# SCH_cherry1_2026-04-12.net
KiCad netlist of a schematic drawn in EasyEDA
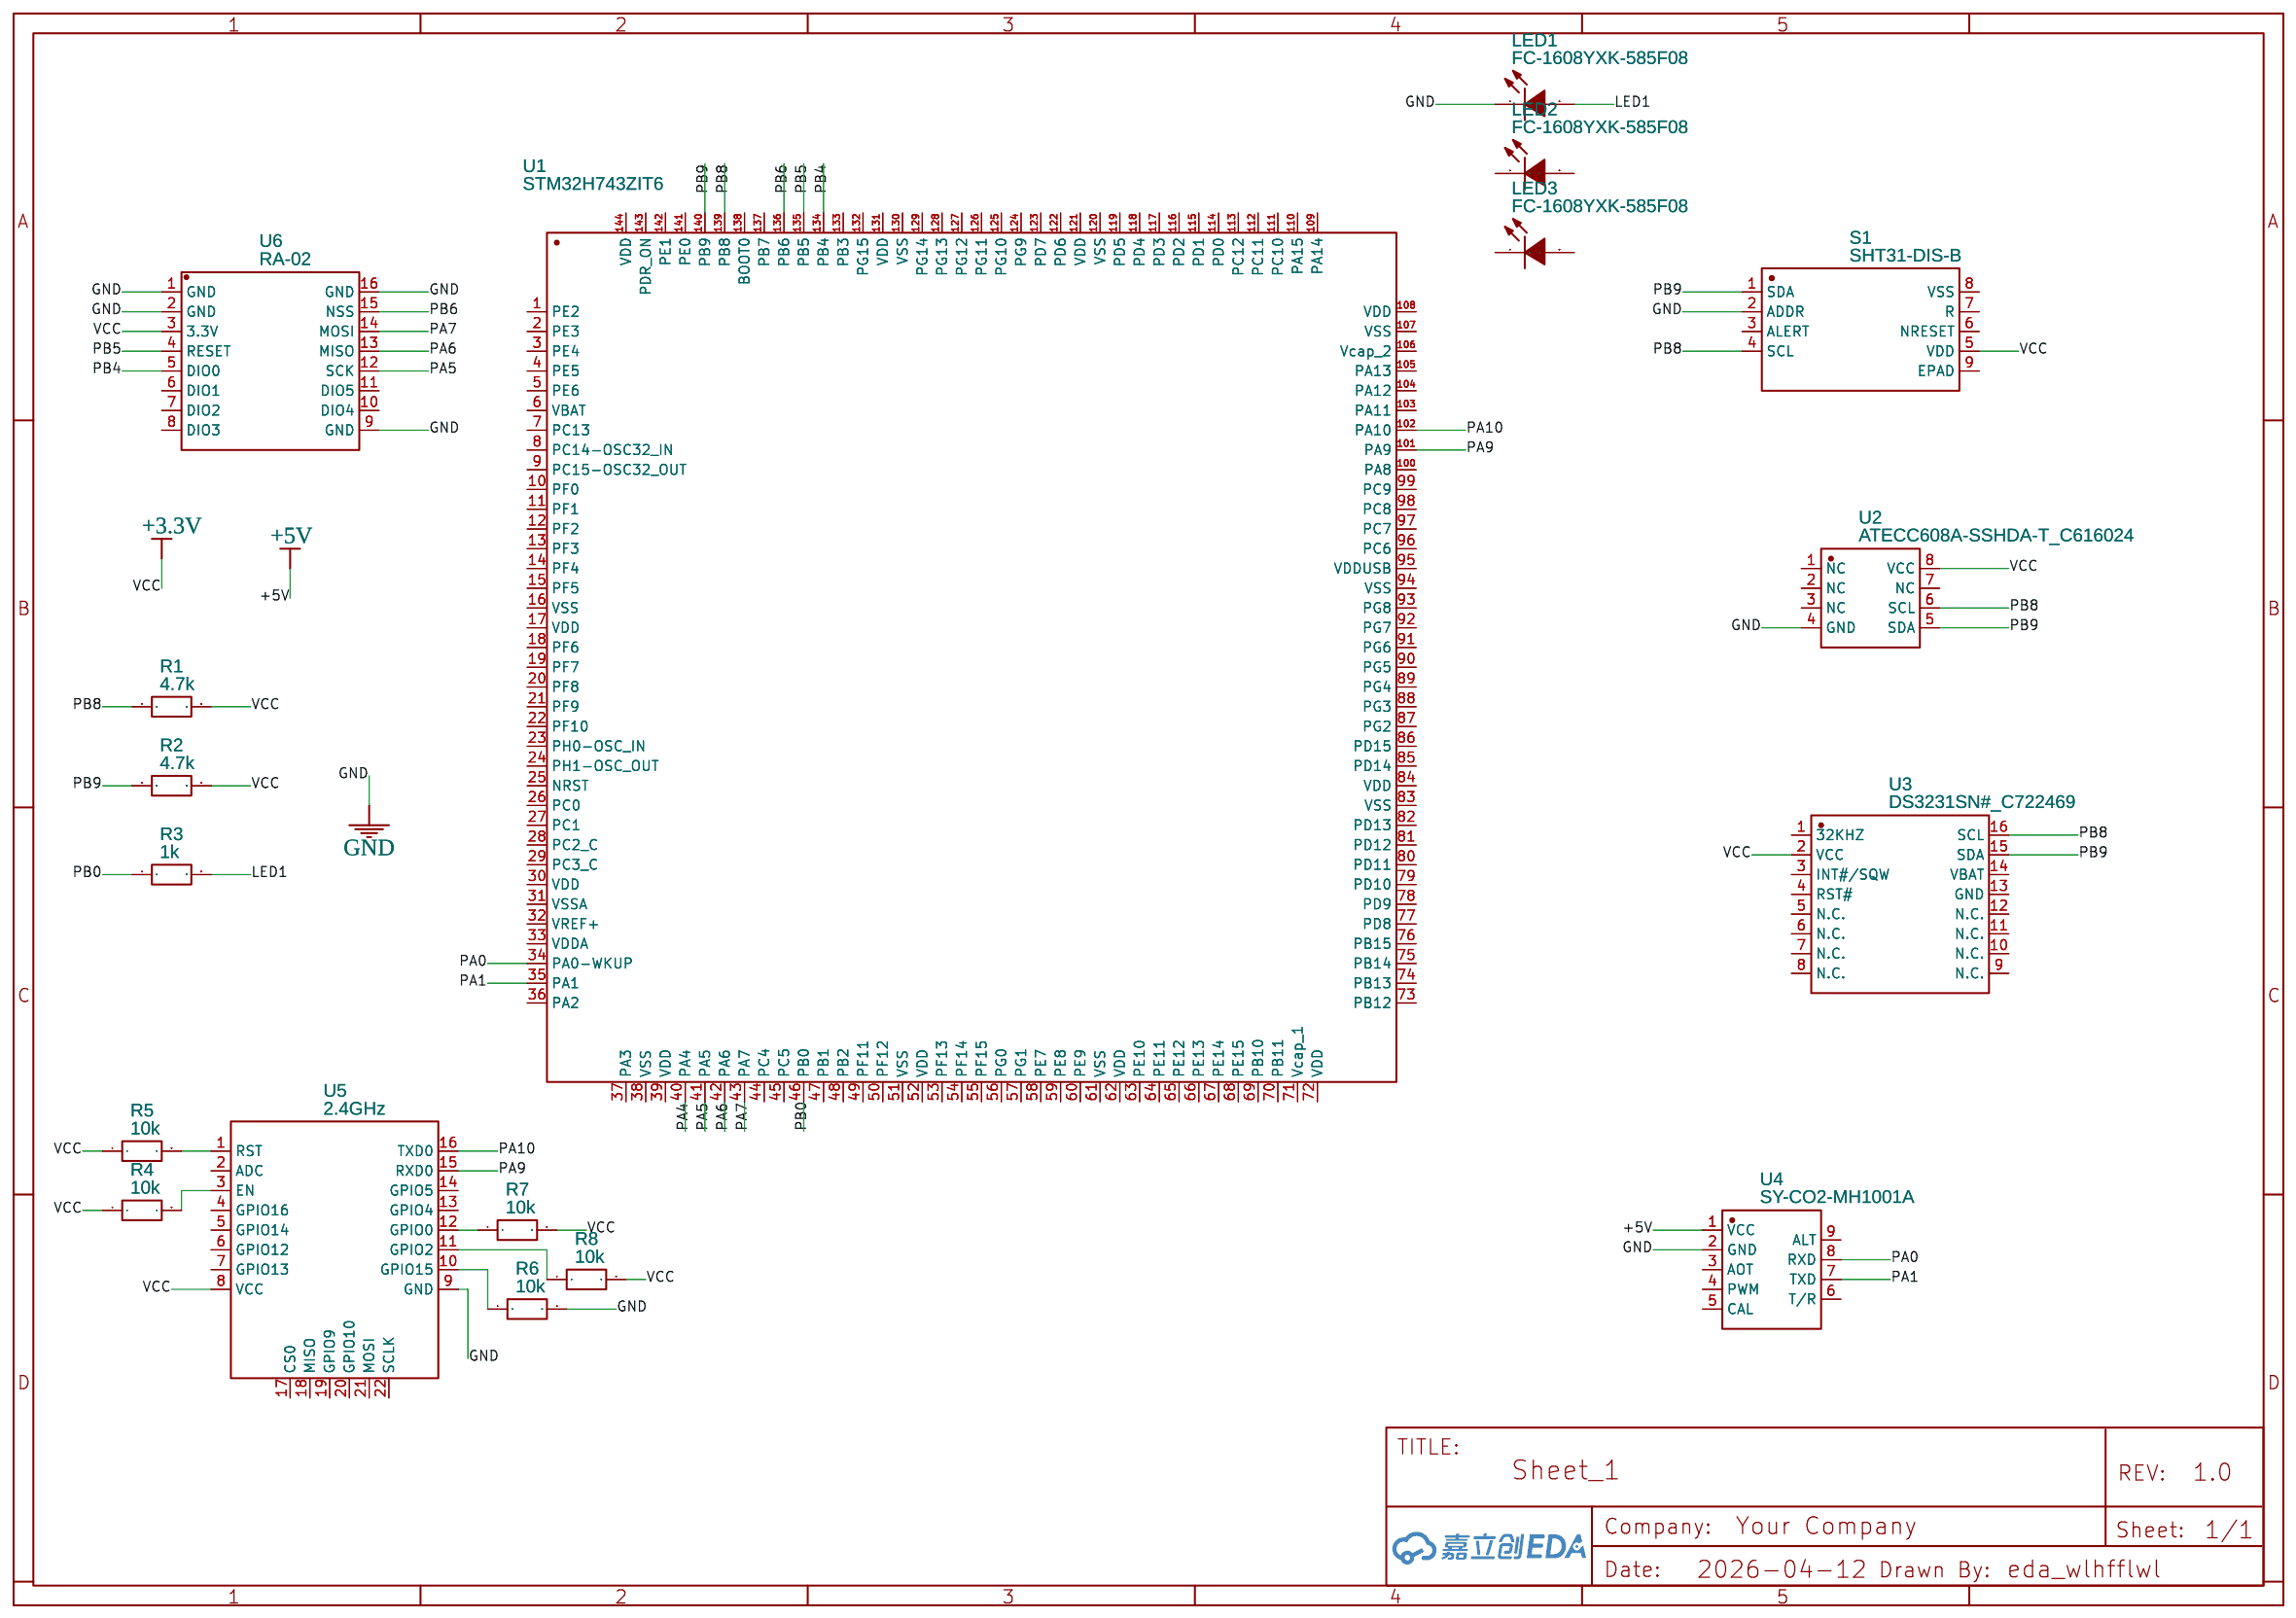
[diagram p0: schematic sheet]

(export (version "E")
  (design (tool "Eeschema 10.0.6"))
  (components
    (comp (ref "LED1")
      (value "FC-1608YXK-585F08")
      (fields (field (name "Manufacturer Part") "NCD0603Y2") (field (name "Manufacturer") "国星光电"))
      (libsource (lib "") (part "FC-1608YXK-585F08"))
    )
    (comp (ref "LED2")
      (value "FC-1608YXK-585F08")
      (fields (field (name "Manufacturer Part") "NCD0603Y2") (field (name "Manufacturer") "国星光电"))
      (libsource (lib "") (part "FC-1608YXK-585F08"))
    )
    (comp (ref "LED3")
      (value "FC-1608YXK-585F08")
      (fields (field (name "Manufacturer Part") "NCD0603Y2") (field (name "Manufacturer") "国星光电"))
      (libsource (lib "") (part "FC-1608YXK-585F08"))
    )
    (comp (ref "R1") (value "4.7k") (libsource (lib "") (part "R_0603_EU")))
    (comp (ref "R2") (value "4.7k") (libsource (lib "") (part "R_0603_EU")))
    (comp (ref "R3") (value "1k") (libsource (lib "") (part "R_0603_EU")))
    (comp (ref "R4") (value "10k") (libsource (lib "") (part "R_0603_EU")))
    (comp (ref "R5") (value "10k") (libsource (lib "") (part "R_0603_EU")))
    (comp (ref "R6") (value "10k") (libsource (lib "") (part "R_0603_EU")))
    (comp (ref "R7") (value "10k") (libsource (lib "") (part "R_0603_EU")))
    (comp (ref "R8") (value "10k") (libsource (lib "") (part "R_0603_EU")))
    (comp (ref "S1")
      (value "SHT31-DIS-B")
      (fields
        (field (name "Manufacturer Part") "SHT31-DIS-B2.5kS")
        (field (name "Manufacturer") "Sensirion(瑞士盛思锐)")
      )
      (libsource (lib "") (part "SHT31-DIS-B"))
    )
    (comp (ref "U1")
      (value "STM32H743ZIT6")
      (fields (field (name "Manufacturer") "ST(意法半导体)"))
      (libsource (lib "") (part "STM32H743ZIT6"))
    )
    (comp (ref "U2")
      (value "ATECC608A-SSHDA-T_C616024")
      (fields
        (field (name "Manufacturer Part") "ATECC608A-SSHDA-T")
        (field (name "Manufacturer") "MICROCHIP(美国微芯)")
      )
      (libsource (lib "") (part "ATECC608A-SSHDA-T_C616024"))
    )
    (comp (ref "U3")
      (value "DS3231SN#_C722469")
      (fields
        (field (name "Manufacturer Part") "DS3231SN#")
        (field (name "Manufacturer") "ADI(亚德诺)/MAXIM(美信)")
      )
      (libsource (lib "") (part "DS3231SN#_C722469"))
    )
    (comp (ref "U4")
      (value "SY-CO2-MH1001A")
      (fields (field (name "Manufacturer Part") "SY-CO2-28BMI") (field (name "Manufacturer") "saiya(赛亚)"))
      (libsource (lib "") (part "SY-CO2-MH1001A"))
    )
    (comp (ref "U5")
      (value "2.4GHz")
      (fields
        (field (name "Manufacturer Part") "ESP-12F(ESP8266MOD)")
        (field (name "Manufacturer") "Ai-Thinker(安信可)")
      )
      (libsource (lib "") (part "ESP-12F(ESP8266MOD)"))
    )
    (comp (ref "U6")
      (value "RA-02")
      (fields (field (name "Manufacturer Part") "Ra-02") (field (name "Manufacturer") "Ai-Thinker(安信可)"))
      (libsource (lib "") (part "RA-02"))
    )
  )
  (nets
    (net (code "1") (name "+3.3V") (class "Default")
      (node (ref "R1") (pin "2") (pinfunction "2_2") (pintype "unspecified"))
      (node (ref "R2") (pin "2") (pinfunction "2_2") (pintype "unspecified"))
      (node (ref "R4") (pin "1") (pinfunction "1_1") (pintype "unspecified"))
      (node (ref "R5") (pin "1") (pinfunction "1_1") (pintype "unspecified"))
      (node (ref "R7") (pin "2") (pinfunction "2_2") (pintype "unspecified"))
      (node (ref "R8") (pin "2") (pinfunction "2_2") (pintype "unspecified"))
      (node (ref "S1") (pin "5") (pinfunction "VDD_5") (pintype "unspecified"))
      (node (ref "U2") (pin "8") (pinfunction "VCC_8") (pintype "unspecified"))
      (node (ref "U3") (pin "2") (pinfunction "VCC_2") (pintype "unspecified"))
      (node (ref "U5") (pin "8") (pinfunction "VCC_8") (pintype "unspecified"))
      (node (ref "U6") (pin "3") (pinfunction "3.3V_3") (pintype "unspecified"))
    )
    (net (code "2") (name "+5V") (class "Default")
      (node (ref "U4") (pin "1") (pinfunction "VCC_1") (pintype "unspecified"))
    )
    (net (code "3") (name "/LED1") (class "Default")
      (node (ref "LED1") (pin "2") (pinfunction "A_2") (pintype "unspecified"))
      (node (ref "R3") (pin "2") (pinfunction "2_2") (pintype "unspecified"))
    )
    (net (code "4") (name "/PA0") (class "Default")
      (node (ref "U1") (pin "34") (pinfunction "PA0-WKUP_34") (pintype "unspecified"))
      (node (ref "U4") (pin "8") (pinfunction "RXD_8") (pintype "unspecified"))
    )
    (net (code "5") (name "/PA1") (class "Default")
      (node (ref "U1") (pin "35") (pinfunction "PA1_35") (pintype "unspecified"))
      (node (ref "U4") (pin "7") (pinfunction "TXD_7") (pintype "unspecified"))
    )
    (net (code "6") (name "/PA4") (class "Default")
      (node (ref "U1") (pin "40") (pinfunction "PA4_40") (pintype "unspecified"))
    )
    (net (code "7") (name "/PA5") (class "Default")
      (node (ref "U1") (pin "41") (pinfunction "PA5_41") (pintype "unspecified"))
      (node (ref "U6") (pin "12") (pinfunction "SCK_12") (pintype "unspecified"))
    )
    (net (code "8") (name "/PA6") (class "Default")
      (node (ref "U1") (pin "42") (pinfunction "PA6_42") (pintype "unspecified"))
      (node (ref "U6") (pin "13") (pinfunction "MISO_13") (pintype "unspecified"))
    )
    (net (code "9") (name "/PA7") (class "Default")
      (node (ref "U1") (pin "43") (pinfunction "PA7_43") (pintype "unspecified"))
      (node (ref "U6") (pin "14") (pinfunction "MOSI_14") (pintype "unspecified"))
    )
    (net (code "10") (name "/PA9") (class "Default")
      (node (ref "U1") (pin "101") (pinfunction "PA9_101") (pintype "unspecified"))
      (node (ref "U5") (pin "15") (pinfunction "RXD0_15") (pintype "unspecified"))
    )
    (net (code "11") (name "/PA10") (class "Default")
      (node (ref "U1") (pin "102") (pinfunction "PA10_102") (pintype "unspecified"))
      (node (ref "U5") (pin "16") (pinfunction "TXD0_16") (pintype "unspecified"))
    )
    (net (code "12") (name "/PB0") (class "Default")
      (node (ref "R3") (pin "1") (pinfunction "1_1") (pintype "unspecified"))
      (node (ref "U1") (pin "46") (pinfunction "PB0_46") (pintype "unspecified"))
    )
    (net (code "13") (name "/PB4") (class "Default")
      (node (ref "U1") (pin "134") (pinfunction "PB4_134") (pintype "unspecified"))
      (node (ref "U6") (pin "5") (pinfunction "DIO0_5") (pintype "unspecified"))
    )
    (net (code "14") (name "/PB5") (class "Default")
      (node (ref "U1") (pin "135") (pinfunction "PB5_135") (pintype "unspecified"))
      (node (ref "U6") (pin "4") (pinfunction "RESET_4") (pintype "unspecified"))
    )
    (net (code "15") (name "/PB6") (class "Default")
      (node (ref "U1") (pin "136") (pinfunction "PB6_136") (pintype "unspecified"))
      (node (ref "U6") (pin "15") (pinfunction "NSS_15") (pintype "unspecified"))
    )
    (net (code "16") (name "/PB8") (class "Default")
      (node (ref "R1") (pin "1") (pinfunction "1_1") (pintype "unspecified"))
      (node (ref "S1") (pin "4") (pinfunction "SCL_4") (pintype "unspecified"))
      (node (ref "U1") (pin "139") (pinfunction "PB8_139") (pintype "unspecified"))
      (node (ref "U2") (pin "6") (pinfunction "SCL_6") (pintype "unspecified"))
      (node (ref "U3") (pin "16") (pinfunction "SCL_16") (pintype "unspecified"))
    )
    (net (code "17") (name "/PB9") (class "Default")
      (node (ref "R2") (pin "1") (pinfunction "1_1") (pintype "unspecified"))
      (node (ref "S1") (pin "1") (pinfunction "SDA_1") (pintype "unspecified"))
      (node (ref "U1") (pin "140") (pinfunction "PB9_140") (pintype "unspecified"))
      (node (ref "U2") (pin "5") (pinfunction "SDA_5") (pintype "unspecified"))
      (node (ref "U3") (pin "15") (pinfunction "SDA_15") (pintype "unspecified"))
    )
    (net (code "18") (name "GND") (class "Default")
      (node (ref "LED1") (pin "1") (pinfunction "K_1") (pintype "unspecified"))
      (node (ref "R6") (pin "2") (pinfunction "2_2") (pintype "unspecified"))
      (node (ref "S1") (pin "2") (pinfunction "ADDR_2") (pintype "unspecified"))
      (node (ref "U2") (pin "4") (pinfunction "GND_4") (pintype "unspecified"))
      (node (ref "U4") (pin "2") (pinfunction "GND_2") (pintype "unspecified"))
      (node (ref "U5") (pin "9") (pinfunction "GND_9") (pintype "unspecified"))
      (node (ref "U6") (pin "1") (pinfunction "GND_1") (pintype "unspecified"))
      (node (ref "U6") (pin "16") (pinfunction "GND_16") (pintype "unspecified"))
      (node (ref "U6") (pin "2") (pinfunction "GND_2") (pintype "unspecified"))
      (node (ref "U6") (pin "9") (pinfunction "GND_9") (pintype "unspecified"))
    )
    (net (code "19") (name "Net-(U5-EN)") (class "Default")
      (node (ref "R4") (pin "2") (pinfunction "2_2") (pintype "unspecified"))
      (node (ref "U5") (pin "3") (pinfunction "EN_3") (pintype "unspecified"))
    )
    (net (code "20") (name "Net-(U5-GPIO0)") (class "Default")
      (node (ref "R7") (pin "1") (pinfunction "1_1") (pintype "unspecified"))
      (node (ref "U5") (pin "12") (pinfunction "GPIO0_12") (pintype "unspecified"))
    )
    (net (code "21") (name "Net-(U5-GPIO2)") (class "Default")
      (node (ref "R8") (pin "1") (pinfunction "1_1") (pintype "unspecified"))
      (node (ref "U5") (pin "11") (pinfunction "GPIO2_11") (pintype "unspecified"))
    )
    (net (code "22") (name "Net-(U5-GPIO15)") (class "Default")
      (node (ref "R6") (pin "1") (pinfunction "1_1") (pintype "unspecified"))
      (node (ref "U5") (pin "10") (pinfunction "GPIO15_10") (pintype "unspecified"))
    )
    (net (code "23") (name "Net-(U5-RST)") (class "Default")
      (node (ref "R5") (pin "2") (pinfunction "2_2") (pintype "unspecified"))
      (node (ref "U5") (pin "1") (pinfunction "RST_1") (pintype "unspecified"))
    )
    (net (code "24") (name "unconnected-(LED2-A-Pad2)") (class "Default")
      (node (ref "LED2") (pin "2") (pinfunction "A_2") (pintype "unspecified"))
    )
    (net (code "25") (name "unconnected-(LED2-K-Pad1)") (class "Default")
      (node (ref "LED2") (pin "1") (pinfunction "K_1") (pintype "unspecified"))
    )
    (net (code "26") (name "unconnected-(LED3-A-Pad2)") (class "Default")
      (node (ref "LED3") (pin "2") (pinfunction "A_2") (pintype "unspecified"))
    )
    (net (code "27") (name "unconnected-(LED3-K-Pad1)") (class "Default")
      (node (ref "LED3") (pin "1") (pinfunction "K_1") (pintype "unspecified"))
    )
    (net (code "28") (name "unconnected-(S1-ALERT-Pad3)") (class "Default")
      (node (ref "S1") (pin "3") (pinfunction "ALERT_3") (pintype "unspecified"))
    )
    (net (code "29") (name "unconnected-(S1-EPAD-Pad9)") (class "Default")
      (node (ref "S1") (pin "9") (pinfunction "EPAD_9") (pintype "unspecified"))
    )
    (net (code "30") (name "unconnected-(S1-NRESET-Pad6)") (class "Default")
      (node (ref "S1") (pin "6") (pinfunction "NRESET_6") (pintype "unspecified"))
    )
    (net (code "31") (name "unconnected-(S1-R-Pad7)") (class "Default")
      (node (ref "S1") (pin "7") (pinfunction "R_7") (pintype "unspecified"))
    )
    (net (code "32") (name "unconnected-(S1-VSS-Pad8)") (class "Default")
      (node (ref "S1") (pin "8") (pinfunction "VSS_8") (pintype "unspecified"))
    )
    (net (code "33") (name "unconnected-(U1-BOOT0-Pad138)") (class "Default")
      (node (ref "U1") (pin "138") (pinfunction "BOOT0_138") (pintype "unspecified"))
    )
    (net (code "34") (name "unconnected-(U1-NRST-Pad25)") (class "Default")
      (node (ref "U1") (pin "25") (pinfunction "NRST_25") (pintype "unspecified"))
    )
    (net (code "35") (name "unconnected-(U1-PA2-Pad36)") (class "Default")
      (node (ref "U1") (pin "36") (pinfunction "PA2_36") (pintype "unspecified"))
    )
    (net (code "36") (name "unconnected-(U1-PA3-Pad37)") (class "Default")
      (node (ref "U1") (pin "37") (pinfunction "PA3_37") (pintype "unspecified"))
    )
    (net (code "37") (name "unconnected-(U1-PA8-Pad100)") (class "Default")
      (node (ref "U1") (pin "100") (pinfunction "PA8_100") (pintype "unspecified"))
    )
    (net (code "38") (name "unconnected-(U1-PA11-Pad103)") (class "Default")
      (node (ref "U1") (pin "103") (pinfunction "PA11_103") (pintype "unspecified"))
    )
    (net (code "39") (name "unconnected-(U1-PA12-Pad104)") (class "Default")
      (node (ref "U1") (pin "104") (pinfunction "PA12_104") (pintype "unspecified"))
    )
    (net (code "40") (name "unconnected-(U1-PA13-Pad105)") (class "Default")
      (node (ref "U1") (pin "105") (pinfunction "PA13_105") (pintype "unspecified"))
    )
    (net (code "41") (name "unconnected-(U1-PA14-Pad109)") (class "Default")
      (node (ref "U1") (pin "109") (pinfunction "PA14_109") (pintype "unspecified"))
    )
    (net (code "42") (name "unconnected-(U1-PA15-Pad110)") (class "Default")
      (node (ref "U1") (pin "110") (pinfunction "PA15_110") (pintype "unspecified"))
    )
    (net (code "43") (name "unconnected-(U1-PB1-Pad47)") (class "Default")
      (node (ref "U1") (pin "47") (pinfunction "PB1_47") (pintype "unspecified"))
    )
    (net (code "44") (name "unconnected-(U1-PB2-Pad48)") (class "Default")
      (node (ref "U1") (pin "48") (pinfunction "PB2_48") (pintype "unspecified"))
    )
    (net (code "45") (name "unconnected-(U1-PB3-Pad133)") (class "Default")
      (node (ref "U1") (pin "133") (pinfunction "PB3_133") (pintype "unspecified"))
    )
    (net (code "46") (name "unconnected-(U1-PB7-Pad137)") (class "Default")
      (node (ref "U1") (pin "137") (pinfunction "PB7_137") (pintype "unspecified"))
    )
    (net (code "47") (name "unconnected-(U1-PB10-Pad69)") (class "Default")
      (node (ref "U1") (pin "69") (pinfunction "PB10_69") (pintype "unspecified"))
    )
    (net (code "48") (name "unconnected-(U1-PB11-Pad70)") (class "Default")
      (node (ref "U1") (pin "70") (pinfunction "PB11_70") (pintype "unspecified"))
    )
    (net (code "49") (name "unconnected-(U1-PB12-Pad73)") (class "Default")
      (node (ref "U1") (pin "73") (pinfunction "PB12_73") (pintype "unspecified"))
    )
    (net (code "50") (name "unconnected-(U1-PB13-Pad74)") (class "Default")
      (node (ref "U1") (pin "74") (pinfunction "PB13_74") (pintype "unspecified"))
    )
    (net (code "51") (name "unconnected-(U1-PB14-Pad75)") (class "Default")
      (node (ref "U1") (pin "75") (pinfunction "PB14_75") (pintype "unspecified"))
    )
    (net (code "52") (name "unconnected-(U1-PB15-Pad76)") (class "Default")
      (node (ref "U1") (pin "76") (pinfunction "PB15_76") (pintype "unspecified"))
    )
    (net (code "53") (name "unconnected-(U1-PC0-Pad26)") (class "Default")
      (node (ref "U1") (pin "26") (pinfunction "PC0_26") (pintype "unspecified"))
    )
    (net (code "54") (name "unconnected-(U1-PC1-Pad27)") (class "Default")
      (node (ref "U1") (pin "27") (pinfunction "PC1_27") (pintype "unspecified"))
    )
    (net (code "55") (name "unconnected-(U1-PC2_C-Pad28)") (class "Default")
      (node (ref "U1") (pin "28") (pinfunction "PC2_C_28") (pintype "unspecified"))
    )
    (net (code "56") (name "unconnected-(U1-PC3_C-Pad29)") (class "Default")
      (node (ref "U1") (pin "29") (pinfunction "PC3_C_29") (pintype "unspecified"))
    )
    (net (code "57") (name "unconnected-(U1-PC4-Pad44)") (class "Default")
      (node (ref "U1") (pin "44") (pinfunction "PC4_44") (pintype "unspecified"))
    )
    (net (code "58") (name "unconnected-(U1-PC5-Pad45)") (class "Default")
      (node (ref "U1") (pin "45") (pinfunction "PC5_45") (pintype "unspecified"))
    )
    (net (code "59") (name "unconnected-(U1-PC6-Pad96)") (class "Default")
      (node (ref "U1") (pin "96") (pinfunction "PC6_96") (pintype "unspecified"))
    )
    (net (code "60") (name "unconnected-(U1-PC7-Pad97)") (class "Default")
      (node (ref "U1") (pin "97") (pinfunction "PC7_97") (pintype "unspecified"))
    )
    (net (code "61") (name "unconnected-(U1-PC8-Pad98)") (class "Default")
      (node (ref "U1") (pin "98") (pinfunction "PC8_98") (pintype "unspecified"))
    )
    (net (code "62") (name "unconnected-(U1-PC9-Pad99)") (class "Default")
      (node (ref "U1") (pin "99") (pinfunction "PC9_99") (pintype "unspecified"))
    )
    (net (code "63") (name "unconnected-(U1-PC10-Pad111)") (class "Default")
      (node (ref "U1") (pin "111") (pinfunction "PC10_111") (pintype "unspecified"))
    )
    (net (code "64") (name "unconnected-(U1-PC11-Pad112)") (class "Default")
      (node (ref "U1") (pin "112") (pinfunction "PC11_112") (pintype "unspecified"))
    )
    (net (code "65") (name "unconnected-(U1-PC12-Pad113)") (class "Default")
      (node (ref "U1") (pin "113") (pinfunction "PC12_113") (pintype "unspecified"))
    )
    (net (code "66") (name "unconnected-(U1-PC13-Pad7)") (class "Default")
      (node (ref "U1") (pin "7") (pinfunction "PC13_7") (pintype "unspecified"))
    )
    (net (code "67") (name "unconnected-(U1-PC14-OSC32_IN-Pad8)") (class "Default")
      (node (ref "U1") (pin "8") (pinfunction "PC14-OSC32_IN_8") (pintype "unspecified"))
    )
    (net (code "68") (name "unconnected-(U1-PC15-OSC32_OUT-Pad9)") (class "Default")
      (node (ref "U1") (pin "9") (pinfunction "PC15-OSC32_OUT_9") (pintype "unspecified"))
    )
    (net (code "69") (name "unconnected-(U1-PD0-Pad114)") (class "Default")
      (node (ref "U1") (pin "114") (pinfunction "PD0_114") (pintype "unspecified"))
    )
    (net (code "70") (name "unconnected-(U1-PD1-Pad115)") (class "Default")
      (node (ref "U1") (pin "115") (pinfunction "PD1_115") (pintype "unspecified"))
    )
    (net (code "71") (name "unconnected-(U1-PD2-Pad116)") (class "Default")
      (node (ref "U1") (pin "116") (pinfunction "PD2_116") (pintype "unspecified"))
    )
    (net (code "72") (name "unconnected-(U1-PD3-Pad117)") (class "Default")
      (node (ref "U1") (pin "117") (pinfunction "PD3_117") (pintype "unspecified"))
    )
    (net (code "73") (name "unconnected-(U1-PD4-Pad118)") (class "Default")
      (node (ref "U1") (pin "118") (pinfunction "PD4_118") (pintype "unspecified"))
    )
    (net (code "74") (name "unconnected-(U1-PD5-Pad119)") (class "Default")
      (node (ref "U1") (pin "119") (pinfunction "PD5_119") (pintype "unspecified"))
    )
    (net (code "75") (name "unconnected-(U1-PD6-Pad122)") (class "Default")
      (node (ref "U1") (pin "122") (pinfunction "PD6_122") (pintype "unspecified"))
    )
    (net (code "76") (name "unconnected-(U1-PD7-Pad123)") (class "Default")
      (node (ref "U1") (pin "123") (pinfunction "PD7_123") (pintype "unspecified"))
    )
    (net (code "77") (name "unconnected-(U1-PD8-Pad77)") (class "Default")
      (node (ref "U1") (pin "77") (pinfunction "PD8_77") (pintype "unspecified"))
    )
    (net (code "78") (name "unconnected-(U1-PD9-Pad78)") (class "Default")
      (node (ref "U1") (pin "78") (pinfunction "PD9_78") (pintype "unspecified"))
    )
    (net (code "79") (name "unconnected-(U1-PD10-Pad79)") (class "Default")
      (node (ref "U1") (pin "79") (pinfunction "PD10_79") (pintype "unspecified"))
    )
    (net (code "80") (name "unconnected-(U1-PD11-Pad80)") (class "Default")
      (node (ref "U1") (pin "80") (pinfunction "PD11_80") (pintype "unspecified"))
    )
    (net (code "81") (name "unconnected-(U1-PD12-Pad81)") (class "Default")
      (node (ref "U1") (pin "81") (pinfunction "PD12_81") (pintype "unspecified"))
    )
    (net (code "82") (name "unconnected-(U1-PD13-Pad82)") (class "Default")
      (node (ref "U1") (pin "82") (pinfunction "PD13_82") (pintype "unspecified"))
    )
    (net (code "83") (name "unconnected-(U1-PD14-Pad85)") (class "Default")
      (node (ref "U1") (pin "85") (pinfunction "PD14_85") (pintype "unspecified"))
    )
    (net (code "84") (name "unconnected-(U1-PD15-Pad86)") (class "Default")
      (node (ref "U1") (pin "86") (pinfunction "PD15_86") (pintype "unspecified"))
    )
    (net (code "85") (name "unconnected-(U1-PDR_ON-Pad143)") (class "Default")
      (node (ref "U1") (pin "143") (pinfunction "PDR_ON_143") (pintype "unspecified"))
    )
    (net (code "86") (name "unconnected-(U1-PE0-Pad141)") (class "Default")
      (node (ref "U1") (pin "141") (pinfunction "PE0_141") (pintype "unspecified"))
    )
    (net (code "87") (name "unconnected-(U1-PE1-Pad142)") (class "Default")
      (node (ref "U1") (pin "142") (pinfunction "PE1_142") (pintype "unspecified"))
    )
    (net (code "88") (name "unconnected-(U1-PE2-Pad1)") (class "Default")
      (node (ref "U1") (pin "1") (pinfunction "PE2_1") (pintype "unspecified"))
    )
    (net (code "89") (name "unconnected-(U1-PE3-Pad2)") (class "Default")
      (node (ref "U1") (pin "2") (pinfunction "PE3_2") (pintype "unspecified"))
    )
    (net (code "90") (name "unconnected-(U1-PE4-Pad3)") (class "Default")
      (node (ref "U1") (pin "3") (pinfunction "PE4_3") (pintype "unspecified"))
    )
    (net (code "91") (name "unconnected-(U1-PE5-Pad4)") (class "Default")
      (node (ref "U1") (pin "4") (pinfunction "PE5_4") (pintype "unspecified"))
    )
    (net (code "92") (name "unconnected-(U1-PE6-Pad5)") (class "Default")
      (node (ref "U1") (pin "5") (pinfunction "PE6_5") (pintype "unspecified"))
    )
    (net (code "93") (name "unconnected-(U1-PE7-Pad58)") (class "Default")
      (node (ref "U1") (pin "58") (pinfunction "PE7_58") (pintype "unspecified"))
    )
    (net (code "94") (name "unconnected-(U1-PE8-Pad59)") (class "Default")
      (node (ref "U1") (pin "59") (pinfunction "PE8_59") (pintype "unspecified"))
    )
    (net (code "95") (name "unconnected-(U1-PE9-Pad60)") (class "Default")
      (node (ref "U1") (pin "60") (pinfunction "PE9_60") (pintype "unspecified"))
    )
    (net (code "96") (name "unconnected-(U1-PE10-Pad63)") (class "Default")
      (node (ref "U1") (pin "63") (pinfunction "PE10_63") (pintype "unspecified"))
    )
    (net (code "97") (name "unconnected-(U1-PE11-Pad64)") (class "Default")
      (node (ref "U1") (pin "64") (pinfunction "PE11_64") (pintype "unspecified"))
    )
    (net (code "98") (name "unconnected-(U1-PE12-Pad65)") (class "Default")
      (node (ref "U1") (pin "65") (pinfunction "PE12_65") (pintype "unspecified"))
    )
    (net (code "99") (name "unconnected-(U1-PE13-Pad66)") (class "Default")
      (node (ref "U1") (pin "66") (pinfunction "PE13_66") (pintype "unspecified"))
    )
    (net (code "100") (name "unconnected-(U1-PE14-Pad67)") (class "Default")
      (node (ref "U1") (pin "67") (pinfunction "PE14_67") (pintype "unspecified"))
    )
    (net (code "101") (name "unconnected-(U1-PE15-Pad68)") (class "Default")
      (node (ref "U1") (pin "68") (pinfunction "PE15_68") (pintype "unspecified"))
    )
    (net (code "102") (name "unconnected-(U1-PF0-Pad10)") (class "Default")
      (node (ref "U1") (pin "10") (pinfunction "PF0_10") (pintype "unspecified"))
    )
    (net (code "103") (name "unconnected-(U1-PF1-Pad11)") (class "Default")
      (node (ref "U1") (pin "11") (pinfunction "PF1_11") (pintype "unspecified"))
    )
    (net (code "104") (name "unconnected-(U1-PF2-Pad12)") (class "Default")
      (node (ref "U1") (pin "12") (pinfunction "PF2_12") (pintype "unspecified"))
    )
    (net (code "105") (name "unconnected-(U1-PF3-Pad13)") (class "Default")
      (node (ref "U1") (pin "13") (pinfunction "PF3_13") (pintype "unspecified"))
    )
    (net (code "106") (name "unconnected-(U1-PF4-Pad14)") (class "Default")
      (node (ref "U1") (pin "14") (pinfunction "PF4_14") (pintype "unspecified"))
    )
    (net (code "107") (name "unconnected-(U1-PF5-Pad15)") (class "Default")
      (node (ref "U1") (pin "15") (pinfunction "PF5_15") (pintype "unspecified"))
    )
    (net (code "108") (name "unconnected-(U1-PF6-Pad18)") (class "Default")
      (node (ref "U1") (pin "18") (pinfunction "PF6_18") (pintype "unspecified"))
    )
    (net (code "109") (name "unconnected-(U1-PF7-Pad19)") (class "Default")
      (node (ref "U1") (pin "19") (pinfunction "PF7_19") (pintype "unspecified"))
    )
    (net (code "110") (name "unconnected-(U1-PF8-Pad20)") (class "Default")
      (node (ref "U1") (pin "20") (pinfunction "PF8_20") (pintype "unspecified"))
    )
    (net (code "111") (name "unconnected-(U1-PF9-Pad21)") (class "Default")
      (node (ref "U1") (pin "21") (pinfunction "PF9_21") (pintype "unspecified"))
    )
    (net (code "112") (name "unconnected-(U1-PF10-Pad22)") (class "Default")
      (node (ref "U1") (pin "22") (pinfunction "PF10_22") (pintype "unspecified"))
    )
    (net (code "113") (name "unconnected-(U1-PF11-Pad49)") (class "Default")
      (node (ref "U1") (pin "49") (pinfunction "PF11_49") (pintype "unspecified"))
    )
    (net (code "114") (name "unconnected-(U1-PF12-Pad50)") (class "Default")
      (node (ref "U1") (pin "50") (pinfunction "PF12_50") (pintype "unspecified"))
    )
    (net (code "115") (name "unconnected-(U1-PF13-Pad53)") (class "Default")
      (node (ref "U1") (pin "53") (pinfunction "PF13_53") (pintype "unspecified"))
    )
    (net (code "116") (name "unconnected-(U1-PF14-Pad54)") (class "Default")
      (node (ref "U1") (pin "54") (pinfunction "PF14_54") (pintype "unspecified"))
    )
    (net (code "117") (name "unconnected-(U1-PF15-Pad55)") (class "Default")
      (node (ref "U1") (pin "55") (pinfunction "PF15_55") (pintype "unspecified"))
    )
    (net (code "118") (name "unconnected-(U1-PG0-Pad56)") (class "Default")
      (node (ref "U1") (pin "56") (pinfunction "PG0_56") (pintype "unspecified"))
    )
    (net (code "119") (name "unconnected-(U1-PG1-Pad57)") (class "Default")
      (node (ref "U1") (pin "57") (pinfunction "PG1_57") (pintype "unspecified"))
    )
    (net (code "120") (name "unconnected-(U1-PG2-Pad87)") (class "Default")
      (node (ref "U1") (pin "87") (pinfunction "PG2_87") (pintype "unspecified"))
    )
    (net (code "121") (name "unconnected-(U1-PG3-Pad88)") (class "Default")
      (node (ref "U1") (pin "88") (pinfunction "PG3_88") (pintype "unspecified"))
    )
    (net (code "122") (name "unconnected-(U1-PG4-Pad89)") (class "Default")
      (node (ref "U1") (pin "89") (pinfunction "PG4_89") (pintype "unspecified"))
    )
    (net (code "123") (name "unconnected-(U1-PG5-Pad90)") (class "Default")
      (node (ref "U1") (pin "90") (pinfunction "PG5_90") (pintype "unspecified"))
    )
    (net (code "124") (name "unconnected-(U1-PG6-Pad91)") (class "Default")
      (node (ref "U1") (pin "91") (pinfunction "PG6_91") (pintype "unspecified"))
    )
    (net (code "125") (name "unconnected-(U1-PG7-Pad92)") (class "Default")
      (node (ref "U1") (pin "92") (pinfunction "PG7_92") (pintype "unspecified"))
    )
    (net (code "126") (name "unconnected-(U1-PG8-Pad93)") (class "Default")
      (node (ref "U1") (pin "93") (pinfunction "PG8_93") (pintype "unspecified"))
    )
    (net (code "127") (name "unconnected-(U1-PG9-Pad124)") (class "Default")
      (node (ref "U1") (pin "124") (pinfunction "PG9_124") (pintype "unspecified"))
    )
    (net (code "128") (name "unconnected-(U1-PG10-Pad125)") (class "Default")
      (node (ref "U1") (pin "125") (pinfunction "PG10_125") (pintype "unspecified"))
    )
    (net (code "129") (name "unconnected-(U1-PG11-Pad126)") (class "Default")
      (node (ref "U1") (pin "126") (pinfunction "PG11_126") (pintype "unspecified"))
    )
    (net (code "130") (name "unconnected-(U1-PG12-Pad127)") (class "Default")
      (node (ref "U1") (pin "127") (pinfunction "PG12_127") (pintype "unspecified"))
    )
    (net (code "131") (name "unconnected-(U1-PG13-Pad128)") (class "Default")
      (node (ref "U1") (pin "128") (pinfunction "PG13_128") (pintype "unspecified"))
    )
    (net (code "132") (name "unconnected-(U1-PG14-Pad129)") (class "Default")
      (node (ref "U1") (pin "129") (pinfunction "PG14_129") (pintype "unspecified"))
    )
    (net (code "133") (name "unconnected-(U1-PG15-Pad132)") (class "Default")
      (node (ref "U1") (pin "132") (pinfunction "PG15_132") (pintype "unspecified"))
    )
    (net (code "134") (name "unconnected-(U1-PH0-OSC_IN-Pad23)") (class "Default")
      (node (ref "U1") (pin "23") (pinfunction "PH0-OSC_IN_23") (pintype "unspecified"))
    )
    (net (code "135") (name "unconnected-(U1-PH1-OSC_OUT-Pad24)") (class "Default")
      (node (ref "U1") (pin "24") (pinfunction "PH1-OSC_OUT_24") (pintype "unspecified"))
    )
    (net (code "136") (name "unconnected-(U1-VBAT-Pad6)") (class "Default")
      (node (ref "U1") (pin "6") (pinfunction "VBAT_6") (pintype "unspecified"))
    )
    (net (code "137") (name "unconnected-(U1-VDD-Pad17)") (class "Default")
      (node (ref "U1") (pin "17") (pinfunction "VDD_17") (pintype "unspecified"))
    )
    (net (code "138") (name "unconnected-(U1-VDD-Pad30)") (class "Default")
      (node (ref "U1") (pin "30") (pinfunction "VDD_30") (pintype "unspecified"))
    )
    (net (code "139") (name "unconnected-(U1-VDD-Pad39)") (class "Default")
      (node (ref "U1") (pin "39") (pinfunction "VDD_39") (pintype "unspecified"))
    )
    (net (code "140") (name "unconnected-(U1-VDD-Pad52)") (class "Default")
      (node (ref "U1") (pin "52") (pinfunction "VDD_52") (pintype "unspecified"))
    )
    (net (code "141") (name "unconnected-(U1-VDD-Pad62)") (class "Default")
      (node (ref "U1") (pin "62") (pinfunction "VDD_62") (pintype "unspecified"))
    )
    (net (code "142") (name "unconnected-(U1-VDD-Pad72)") (class "Default")
      (node (ref "U1") (pin "72") (pinfunction "VDD_72") (pintype "unspecified"))
    )
    (net (code "143") (name "unconnected-(U1-VDD-Pad84)") (class "Default")
      (node (ref "U1") (pin "84") (pinfunction "VDD_84") (pintype "unspecified"))
    )
    (net (code "144") (name "unconnected-(U1-VDD-Pad108)") (class "Default")
      (node (ref "U1") (pin "108") (pinfunction "VDD_108") (pintype "unspecified"))
    )
    (net (code "145") (name "unconnected-(U1-VDD-Pad121)") (class "Default")
      (node (ref "U1") (pin "121") (pinfunction "VDD_121") (pintype "unspecified"))
    )
    (net (code "146") (name "unconnected-(U1-VDD-Pad131)") (class "Default")
      (node (ref "U1") (pin "131") (pinfunction "VDD_131") (pintype "unspecified"))
    )
    (net (code "147") (name "unconnected-(U1-VDD-Pad144)") (class "Default")
      (node (ref "U1") (pin "144") (pinfunction "VDD_144") (pintype "unspecified"))
    )
    (net (code "148") (name "unconnected-(U1-VDDA-Pad33)") (class "Default")
      (node (ref "U1") (pin "33") (pinfunction "VDDA_33") (pintype "unspecified"))
    )
    (net (code "149") (name "unconnected-(U1-VDDUSB-Pad95)") (class "Default")
      (node (ref "U1") (pin "95") (pinfunction "VDDUSB_95") (pintype "unspecified"))
    )
    (net (code "150") (name "unconnected-(U1-VREF+-Pad32)") (class "Default")
      (node (ref "U1") (pin "32") (pinfunction "VREF+_32") (pintype "unspecified"))
    )
    (net (code "151") (name "unconnected-(U1-VSS-Pad16)") (class "Default")
      (node (ref "U1") (pin "16") (pinfunction "VSS_16") (pintype "unspecified"))
    )
    (net (code "152") (name "unconnected-(U1-VSS-Pad38)") (class "Default")
      (node (ref "U1") (pin "38") (pinfunction "VSS_38") (pintype "unspecified"))
    )
    (net (code "153") (name "unconnected-(U1-VSS-Pad51)") (class "Default")
      (node (ref "U1") (pin "51") (pinfunction "VSS_51") (pintype "unspecified"))
    )
    (net (code "154") (name "unconnected-(U1-VSS-Pad61)") (class "Default")
      (node (ref "U1") (pin "61") (pinfunction "VSS_61") (pintype "unspecified"))
    )
    (net (code "155") (name "unconnected-(U1-VSS-Pad83)") (class "Default")
      (node (ref "U1") (pin "83") (pinfunction "VSS_83") (pintype "unspecified"))
    )
    (net (code "156") (name "unconnected-(U1-VSS-Pad94)") (class "Default")
      (node (ref "U1") (pin "94") (pinfunction "VSS_94") (pintype "unspecified"))
    )
    (net (code "157") (name "unconnected-(U1-VSS-Pad107)") (class "Default")
      (node (ref "U1") (pin "107") (pinfunction "VSS_107") (pintype "unspecified"))
    )
    (net (code "158") (name "unconnected-(U1-VSS-Pad120)") (class "Default")
      (node (ref "U1") (pin "120") (pinfunction "VSS_120") (pintype "unspecified"))
    )
    (net (code "159") (name "unconnected-(U1-VSS-Pad130)") (class "Default")
      (node (ref "U1") (pin "130") (pinfunction "VSS_130") (pintype "unspecified"))
    )
    (net (code "160") (name "unconnected-(U1-VSSA-Pad31)") (class "Default")
      (node (ref "U1") (pin "31") (pinfunction "VSSA_31") (pintype "unspecified"))
    )
    (net (code "161") (name "unconnected-(U1-Vcap_1-Pad71)") (class "Default")
      (node (ref "U1") (pin "71") (pinfunction "Vcap_1_71") (pintype "unspecified"))
    )
    (net (code "162") (name "unconnected-(U1-Vcap_2-Pad106)") (class "Default")
      (node (ref "U1") (pin "106") (pinfunction "Vcap_2_106") (pintype "unspecified"))
    )
    (net (code "163") (name "unconnected-(U2-NC-Pad1)") (class "Default")
      (node (ref "U2") (pin "1") (pinfunction "NC_1") (pintype "unspecified"))
    )
    (net (code "164") (name "unconnected-(U2-NC-Pad2)") (class "Default")
      (node (ref "U2") (pin "2") (pinfunction "NC_2") (pintype "unspecified"))
    )
    (net (code "165") (name "unconnected-(U2-NC-Pad3)") (class "Default")
      (node (ref "U2") (pin "3") (pinfunction "NC_3") (pintype "unspecified"))
    )
    (net (code "166") (name "unconnected-(U2-NC-Pad7)") (class "Default")
      (node (ref "U2") (pin "7") (pinfunction "NC_7") (pintype "unspecified"))
    )
    (net (code "167") (name "unconnected-(U3-32KHZ-Pad1)") (class "Default")
      (node (ref "U3") (pin "1") (pinfunction "32KHZ_1") (pintype "unspecified"))
    )
    (net (code "168") (name "unconnected-(U3-GND-Pad13)") (class "Default")
      (node (ref "U3") (pin "13") (pinfunction "GND_13") (pintype "unspecified"))
    )
    (net (code "169") (name "unconnected-(U3-INT#{slash}SQW-Pad3)") (class "Default")
      (node (ref "U3") (pin "3") (pinfunction "INT#/SQW_3") (pintype "unspecified"))
    )
    (net (code "170") (name "unconnected-(U3-N.C.-Pad5)") (class "Default")
      (node (ref "U3") (pin "5") (pinfunction "N.C._5") (pintype "unspecified"))
    )
    (net (code "171") (name "unconnected-(U3-N.C.-Pad6)") (class "Default")
      (node (ref "U3") (pin "6") (pinfunction "N.C._6") (pintype "unspecified"))
    )
    (net (code "172") (name "unconnected-(U3-N.C.-Pad7)") (class "Default")
      (node (ref "U3") (pin "7") (pinfunction "N.C._7") (pintype "unspecified"))
    )
    (net (code "173") (name "unconnected-(U3-N.C.-Pad8)") (class "Default")
      (node (ref "U3") (pin "8") (pinfunction "N.C._8") (pintype "unspecified"))
    )
    (net (code "174") (name "unconnected-(U3-N.C.-Pad9)") (class "Default")
      (node (ref "U3") (pin "9") (pinfunction "N.C._9") (pintype "unspecified"))
    )
    (net (code "175") (name "unconnected-(U3-N.C.-Pad10)") (class "Default")
      (node (ref "U3") (pin "10") (pinfunction "N.C._10") (pintype "unspecified"))
    )
    (net (code "176") (name "unconnected-(U3-N.C.-Pad11)") (class "Default")
      (node (ref "U3") (pin "11") (pinfunction "N.C._11") (pintype "unspecified"))
    )
    (net (code "177") (name "unconnected-(U3-N.C.-Pad12)") (class "Default")
      (node (ref "U3") (pin "12") (pinfunction "N.C._12") (pintype "unspecified"))
    )
    (net (code "178") (name "unconnected-(U3-RST#-Pad4)") (class "Default")
      (node (ref "U3") (pin "4") (pinfunction "RST#_4") (pintype "unspecified"))
    )
    (net (code "179") (name "unconnected-(U3-VBAT-Pad14)") (class "Default")
      (node (ref "U3") (pin "14") (pinfunction "VBAT_14") (pintype "unspecified"))
    )
    (net (code "180") (name "unconnected-(U4-ALT-Pad9)") (class "Default")
      (node (ref "U4") (pin "9") (pinfunction "ALT_9") (pintype "unspecified"))
    )
    (net (code "181") (name "unconnected-(U4-AOT-Pad3)") (class "Default")
      (node (ref "U4") (pin "3") (pinfunction "AOT_3") (pintype "unspecified"))
    )
    (net (code "182") (name "unconnected-(U4-CAL-Pad5)") (class "Default")
      (node (ref "U4") (pin "5") (pinfunction "CAL_5") (pintype "unspecified"))
    )
    (net (code "183") (name "unconnected-(U4-PWM-Pad4)") (class "Default")
      (node (ref "U4") (pin "4") (pinfunction "PWM_4") (pintype "unspecified"))
    )
    (net (code "184") (name "unconnected-(U4-T{slash}R-Pad6)") (class "Default")
      (node (ref "U4") (pin "6") (pinfunction "T/R_6") (pintype "unspecified"))
    )
    (net (code "185") (name "unconnected-(U5-ADC-Pad2)") (class "Default")
      (node (ref "U5") (pin "2") (pinfunction "ADC_2") (pintype "unspecified"))
    )
    (net (code "186") (name "unconnected-(U5-CS0-Pad17)") (class "Default")
      (node (ref "U5") (pin "17") (pinfunction "CS0_17") (pintype "unspecified"))
    )
    (net (code "187") (name "unconnected-(U5-GPIO4-Pad13)") (class "Default")
      (node (ref "U5") (pin "13") (pinfunction "GPIO4_13") (pintype "unspecified"))
    )
    (net (code "188") (name "unconnected-(U5-GPIO5-Pad14)") (class "Default")
      (node (ref "U5") (pin "14") (pinfunction "GPIO5_14") (pintype "unspecified"))
    )
    (net (code "189") (name "unconnected-(U5-GPIO9-Pad19)") (class "Default")
      (node (ref "U5") (pin "19") (pinfunction "GPIO9_19") (pintype "unspecified"))
    )
    (net (code "190") (name "unconnected-(U5-GPIO10-Pad20)") (class "Default")
      (node (ref "U5") (pin "20") (pinfunction "GPIO10_20") (pintype "unspecified"))
    )
    (net (code "191") (name "unconnected-(U5-GPIO12-Pad6)") (class "Default")
      (node (ref "U5") (pin "6") (pinfunction "GPIO12_6") (pintype "unspecified"))
    )
    (net (code "192") (name "unconnected-(U5-GPIO13-Pad7)") (class "Default")
      (node (ref "U5") (pin "7") (pinfunction "GPIO13_7") (pintype "unspecified"))
    )
    (net (code "193") (name "unconnected-(U5-GPIO14-Pad5)") (class "Default")
      (node (ref "U5") (pin "5") (pinfunction "GPIO14_5") (pintype "unspecified"))
    )
    (net (code "194") (name "unconnected-(U5-GPIO16-Pad4)") (class "Default")
      (node (ref "U5") (pin "4") (pinfunction "GPIO16_4") (pintype "unspecified"))
    )
    (net (code "195") (name "unconnected-(U5-MISO-Pad18)") (class "Default")
      (node (ref "U5") (pin "18") (pinfunction "MISO_18") (pintype "unspecified"))
    )
    (net (code "196") (name "unconnected-(U5-MOSI-Pad21)") (class "Default")
      (node (ref "U5") (pin "21") (pinfunction "MOSI_21") (pintype "unspecified"))
    )
    (net (code "197") (name "unconnected-(U5-SCLK-Pad22)") (class "Default")
      (node (ref "U5") (pin "22") (pinfunction "SCLK_22") (pintype "unspecified"))
    )
    (net (code "198") (name "unconnected-(U6-DIO1-Pad6)") (class "Default")
      (node (ref "U6") (pin "6") (pinfunction "DIO1_6") (pintype "unspecified"))
    )
    (net (code "199") (name "unconnected-(U6-DIO2-Pad7)") (class "Default")
      (node (ref "U6") (pin "7") (pinfunction "DIO2_7") (pintype "unspecified"))
    )
    (net (code "200") (name "unconnected-(U6-DIO3-Pad8)") (class "Default")
      (node (ref "U6") (pin "8") (pinfunction "DIO3_8") (pintype "unspecified"))
    )
    (net (code "201") (name "unconnected-(U6-DIO4-Pad10)") (class "Default")
      (node (ref "U6") (pin "10") (pinfunction "DIO4_10") (pintype "unspecified"))
    )
    (net (code "202") (name "unconnected-(U6-DIO5-Pad11)") (class "Default")
      (node (ref "U6") (pin "11") (pinfunction "DIO5_11") (pintype "unspecified"))
    )
  )
)
